# freezer_alarm.net
KiCad netlist of a schematic drawn in EAGLE
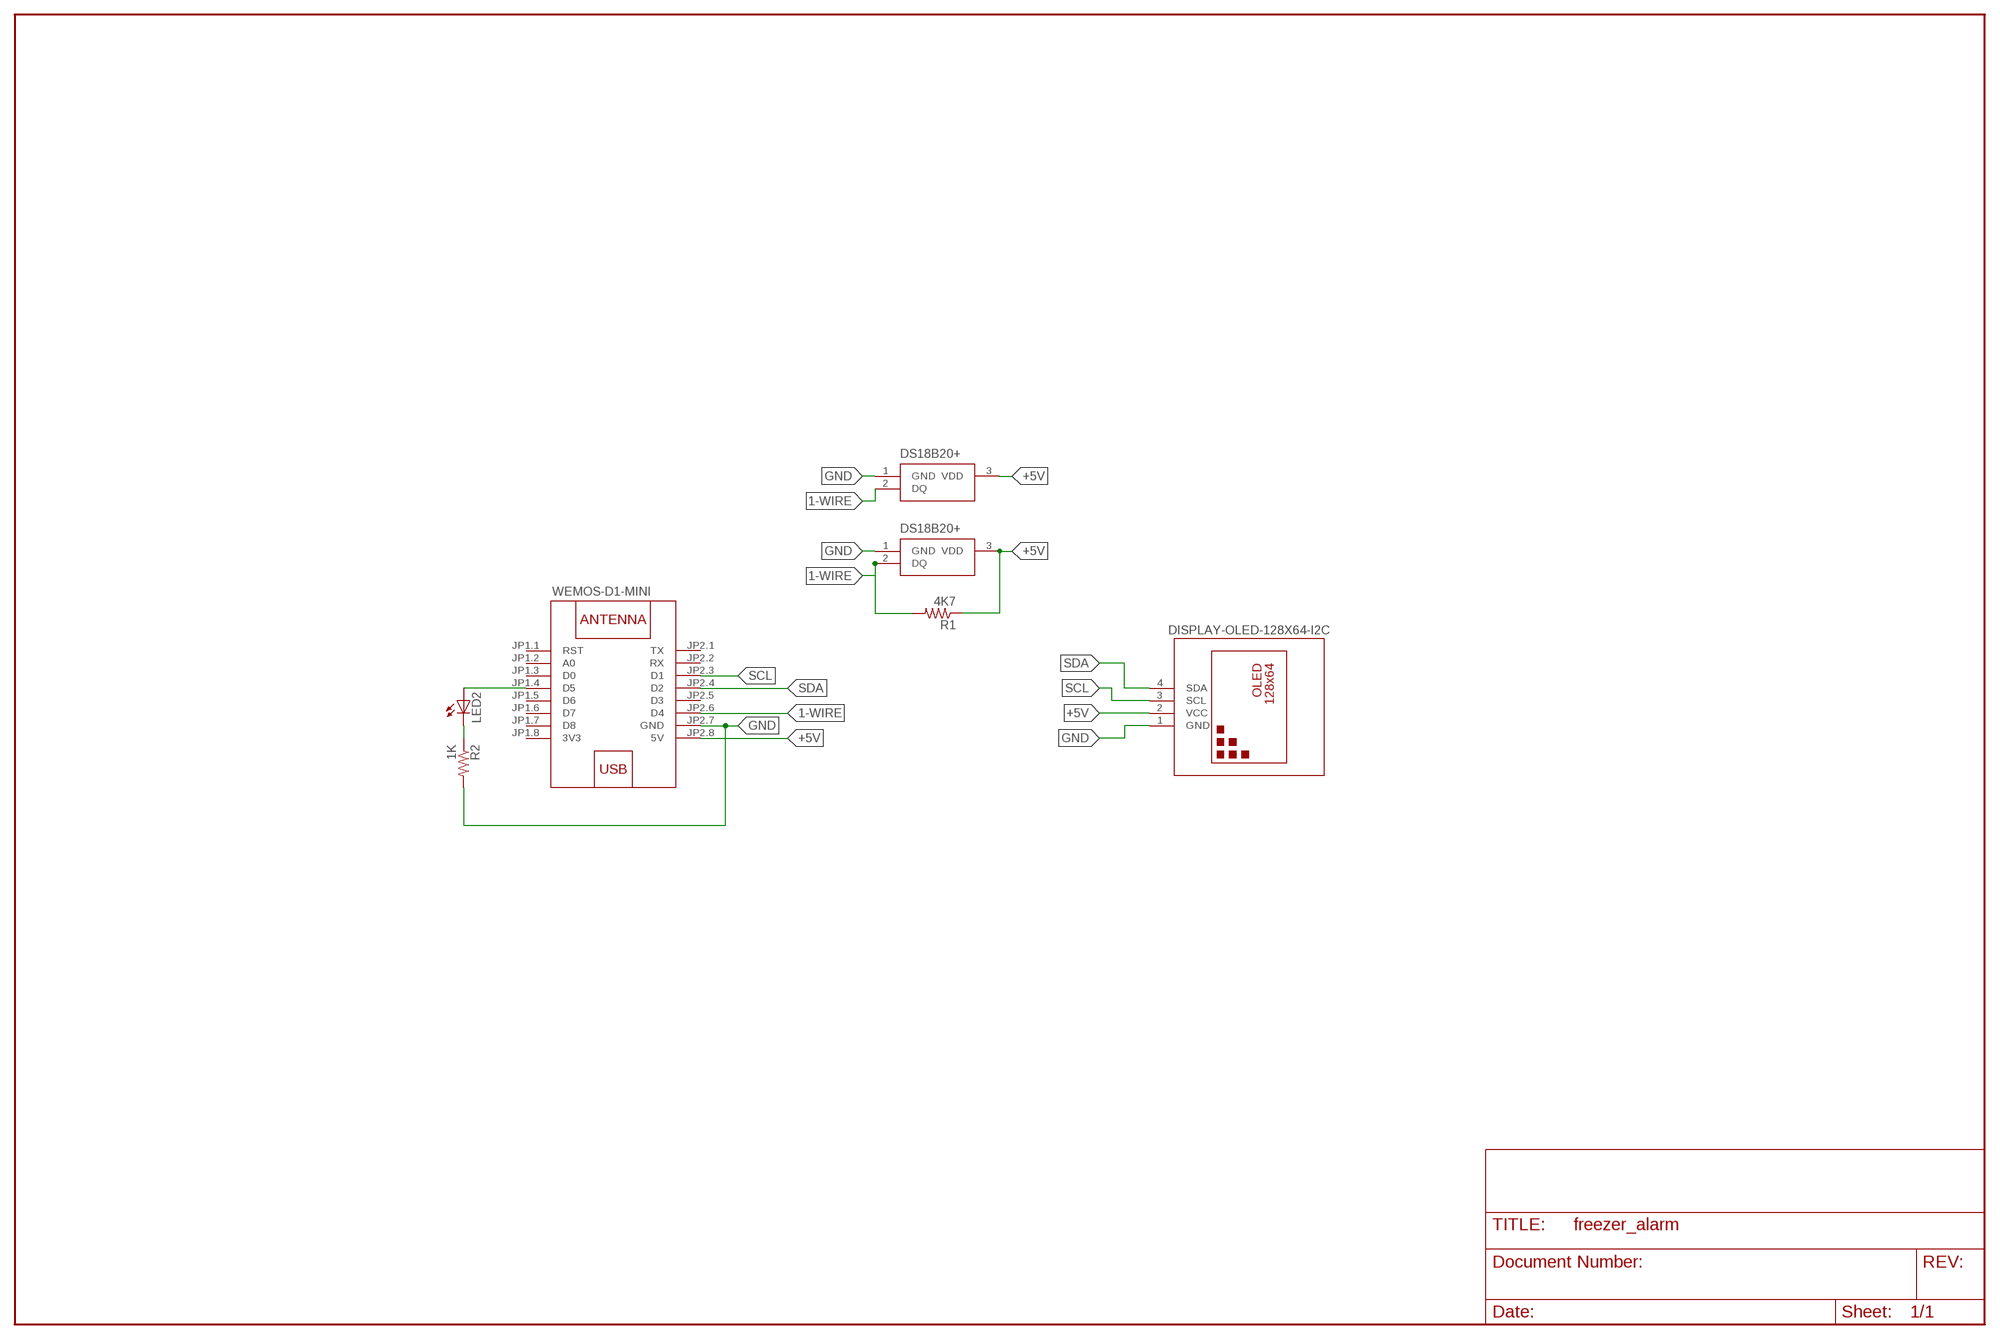
[diagram p0: schematic, sheet 1]

(export (version "E")
  (design (tool "Eeschema 10.0.6"))
  (components
    (comp (ref "DISP")
      (value "DISPLAY-OLED-128X64-I2C")
      (footprint "eagle-import:DISPLAY-OLED-128X64-I2C")
      (libsource (lib "eagle-import") (part "DISPLAY-OLED-128X64-I2C"))
    )
    (comp (ref "IC1")
      (value "DS18B20+")
      (footprint "eagle-import:TO-92")
      (fields (field (name "MOUSER_PART_NUMBER") "700-DS18B20+"))
      (libsource (lib "eagle-import") (part "DS18B20+"))
    )
    (comp (ref "IC2")
      (value "DS18B20+")
      (footprint "eagle-import:TO-92")
      (fields (field (name "MOUSER_PART_NUMBER") "700-DS18B20+"))
      (libsource (lib "eagle-import") (part "DS18B20+"))
    )
    (comp (ref "LED2")
      (value "LED5MM")
      (footprint "eagle-import:LED5MM")
      (libsource (lib "eagle-import") (part "LED5MM"))
    )
    (comp (ref "R1")
      (value "4K7")
      (footprint "eagle-import:0207_10")
      (libsource (lib "eagle-import") (part "R-US_0207/10"))
    )
    (comp (ref "R2")
      (value "1K")
      (footprint "eagle-import:0207_10")
      (libsource (lib "eagle-import") (part "R-US_0207/10"))
    )
    (comp (ref "W1")
      (value "WEMOS-D1-MINI")
      (footprint "eagle-import:WEMOS-D1-MINI")
      (libsource (lib "eagle-import") (part "WEMOS-D1-MINI"))
    )
  )
  (nets
    (net (code "1") (name "+5V") (class "Default")
      (node (ref "DISP") (pin "2") (pinfunction "VCC_2") (pintype "power_in"))
      (node (ref "IC1") (pin "3") (pinfunction "VDD_3") (pintype "power_in"))
      (node (ref "IC2") (pin "3") (pinfunction "VDD_3") (pintype "power_in"))
      (node (ref "R1") (pin "1") (pinfunction "1_1") (pintype "passive"))
      (node (ref "W1") (pin "JP2.8") (pinfunction "5V_JP2.8") (pintype "power_in"))
    )
    (net (code "2") (name "/3V3") (class "Default")
      (node (ref "W1") (pin "JP1.8") (pinfunction "3V3_JP1.8") (pintype "power_in"))
    )
    (net (code "3") (name "1-WIRE") (class "Default")
      (node (ref "IC1") (pin "2") (pinfunction "DQ_2") (pintype "bidirectional"))
      (node (ref "IC2") (pin "2") (pinfunction "DQ_2") (pintype "bidirectional"))
      (node (ref "R1") (pin "2") (pinfunction "2_2") (pintype "passive"))
      (node (ref "W1") (pin "JP2.6") (pinfunction "D4_JP2.6") (pintype "bidirectional"))
    )
    (net (code "4") (name "GND") (class "Default")
      (node (ref "DISP") (pin "1") (pinfunction "GND_1") (pintype "power_in"))
      (node (ref "IC1") (pin "1") (pinfunction "GND_1") (pintype "power_in"))
      (node (ref "IC2") (pin "1") (pinfunction "GND_1") (pintype "power_in"))
      (node (ref "R2") (pin "2") (pinfunction "2_2") (pintype "passive"))
      (node (ref "W1") (pin "JP2.7") (pinfunction "GND_JP2.7") (pintype "power_in"))
    )
    (net (code "5") (name "Net-(LED2-C)") (class "Default")
      (node (ref "LED2") (pin "K") (pinfunction "C_K") (pintype "passive"))
      (node (ref "R2") (pin "1") (pinfunction "1_1") (pintype "passive"))
    )
    (net (code "6") (name "Net-(W1-D5)") (class "Default")
      (node (ref "LED2") (pin "A") (pinfunction "A_A") (pintype "passive"))
      (node (ref "W1") (pin "JP1.4") (pinfunction "D5_JP1.4") (pintype "bidirectional"))
    )
    (net (code "7") (name "SCL") (class "Default")
      (node (ref "DISP") (pin "3") (pinfunction "SCL_3") (pintype "bidirectional"))
      (node (ref "W1") (pin "JP2.3") (pinfunction "D1_JP2.3") (pintype "bidirectional"))
    )
    (net (code "8") (name "SDA") (class "Default")
      (node (ref "DISP") (pin "4") (pinfunction "SDA_4") (pintype "bidirectional"))
      (node (ref "W1") (pin "JP2.4") (pinfunction "D2_JP2.4") (pintype "bidirectional"))
    )
    (net (code "9") (name "unconnected-(W1-A0-PadJP1.2)") (class "Default")
      (node (ref "W1") (pin "JP1.2") (pinfunction "A0_JP1.2") (pintype "bidirectional"))
    )
    (net (code "10") (name "unconnected-(W1-D0-PadJP1.3)") (class "Default")
      (node (ref "W1") (pin "JP1.3") (pinfunction "D0_JP1.3") (pintype "bidirectional"))
    )
    (net (code "11") (name "unconnected-(W1-D3-PadJP2.5)") (class "Default")
      (node (ref "W1") (pin "JP2.5") (pinfunction "D3_JP2.5") (pintype "bidirectional"))
    )
    (net (code "12") (name "unconnected-(W1-D6-PadJP1.5)") (class "Default")
      (node (ref "W1") (pin "JP1.5") (pinfunction "D6_JP1.5") (pintype "bidirectional"))
    )
    (net (code "13") (name "unconnected-(W1-D7-PadJP1.6)") (class "Default")
      (node (ref "W1") (pin "JP1.6") (pinfunction "D7_JP1.6") (pintype "bidirectional"))
    )
    (net (code "14") (name "unconnected-(W1-D8-PadJP1.7)") (class "Default")
      (node (ref "W1") (pin "JP1.7") (pinfunction "D8_JP1.7") (pintype "bidirectional"))
    )
    (net (code "15") (name "unconnected-(W1-RST-PadJP1.1)") (class "Default")
      (node (ref "W1") (pin "JP1.1") (pinfunction "RST_JP1.1") (pintype "bidirectional"))
    )
    (net (code "16") (name "unconnected-(W1-RX-PadJP2.2)") (class "Default")
      (node (ref "W1") (pin "JP2.2") (pinfunction "RX_JP2.2") (pintype "bidirectional"))
    )
    (net (code "17") (name "unconnected-(W1-TX-PadJP2.1)") (class "Default")
      (node (ref "W1") (pin "JP2.1") (pinfunction "TX_JP2.1") (pintype "bidirectional"))
    )
  )
)
